# STM32F103.net
KiCad netlist of a schematic drawn in Altium Designer
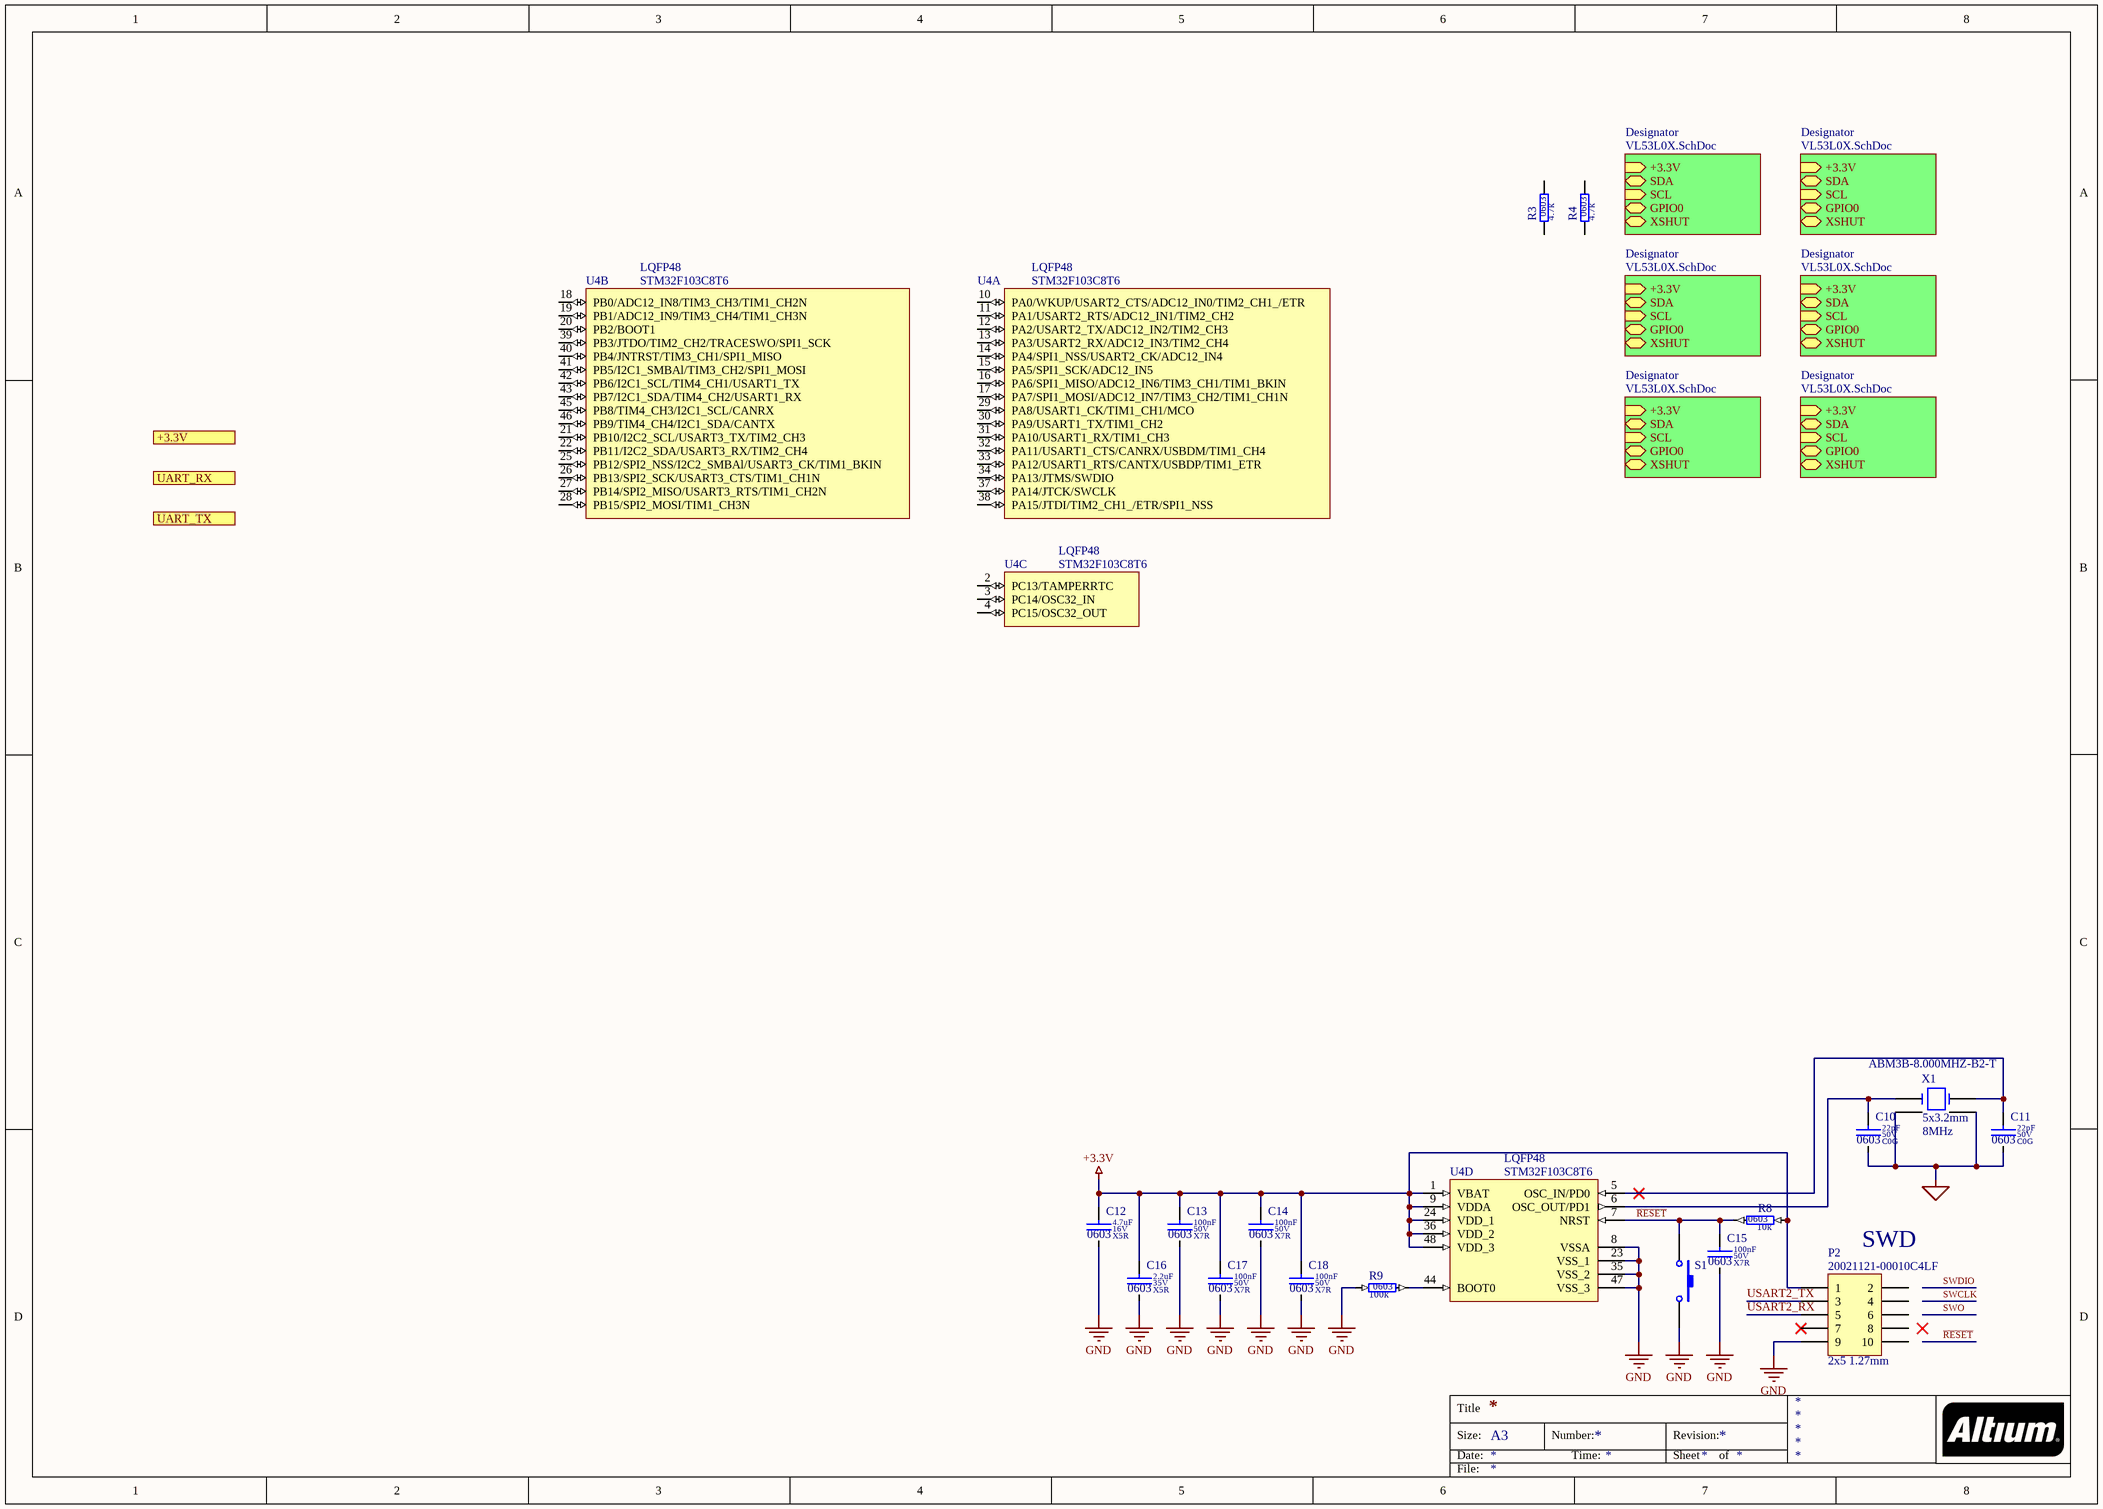
[diagram p0: STM32F103.SchDoc]

(export (version "E")
  (design (tool "Eeschema 10.0.6"))
  (components
    (comp (ref "C10")
      (value "22pF")
      (footprint "C_0603_1608")
      (description "Capacitor")
      (fields
        (field (name "DIELECTRIC") "C0G")
        (field (name "VOLTAGE") "50V")
        (field (name "SCH_FOOTPRINT") "0603")
        (field (name "PART NUMBER") "C_22pF_50V_C0G_0603_5")
        (field (name "MANUFACTURER") "Yageo")
      )
      (libsource (lib "Library") (part "C"))
    )
    (comp (ref "C11")
      (value "22pF")
      (footprint "C_0603_1608")
      (description "Capacitor")
      (fields
        (field (name "DIELECTRIC") "C0G")
        (field (name "VOLTAGE") "50V")
        (field (name "SCH_FOOTPRINT") "0603")
        (field (name "PART NUMBER") "C_22pF_50V_C0G_0603_5")
        (field (name "MANUFACTURER") "Yageo")
      )
      (libsource (lib "Library") (part "C"))
    )
    (comp (ref "C12")
      (value "4.7uF")
      (footprint "C_0603_1608")
      (description "Capacitor")
      (fields
        (field (name "DIELECTRIC") "X5R")
        (field (name "VOLTAGE") "16V")
        (field (name "SCH_FOOTPRINT") "0603")
        (field (name "PART NUMBER") "C_4.7uF_16V_X5R_0603_10")
        (field (name "MANUFACTURER") "Murata")
      )
      (libsource (lib "Library") (part "C"))
    )
    (comp (ref "C13")
      (value "100nF")
      (footprint "C_0603_1608")
      (description "Capacitor")
      (fields
        (field (name "DIELECTRIC") "X7R")
        (field (name "VOLTAGE") "50V")
        (field (name "SCH_FOOTPRINT") "0603")
        (field (name "PART NUMBER") "C_100nF_50V_X7R_0603_5")
        (field (name "MANUFACTURER") "Samsung")
      )
      (libsource (lib "Library") (part "C"))
    )
    (comp (ref "C14")
      (value "100nF")
      (footprint "C_0603_1608")
      (description "Capacitor")
      (fields
        (field (name "DIELECTRIC") "X7R")
        (field (name "VOLTAGE") "50V")
        (field (name "SCH_FOOTPRINT") "0603")
        (field (name "PART NUMBER") "C_100nF_50V_X7R_0603_5")
        (field (name "MANUFACTURER") "Samsung")
      )
      (libsource (lib "Library") (part "C"))
    )
    (comp (ref "C15")
      (value "100nF")
      (footprint "C_0603_1608")
      (description "Capacitor")
      (fields
        (field (name "DIELECTRIC") "X7R")
        (field (name "VOLTAGE") "50V")
        (field (name "SCH_FOOTPRINT") "0603")
        (field (name "PART NUMBER") "C_100nF_50V_X7R_0603_5")
        (field (name "MANUFACTURER") "Samsung")
      )
      (libsource (lib "Library") (part "C"))
    )
    (comp (ref "C16")
      (value "2.2uF")
      (footprint "C_0603_1608")
      (description "Capacitor")
      (fields
        (field (name "DIELECTRIC") "X5R")
        (field (name "VOLTAGE") "35V")
        (field (name "SCH_FOOTPRINT") "0603")
        (field (name "PART NUMBER") "C_2.2uF_35V_X5R_0603_10")
        (field (name "MANUFACTURER") "Murata")
      )
      (libsource (lib "Library") (part "C"))
    )
    (comp (ref "C17")
      (value "100nF")
      (footprint "C_0603_1608")
      (description "Capacitor")
      (fields
        (field (name "DIELECTRIC") "X7R")
        (field (name "VOLTAGE") "50V")
        (field (name "SCH_FOOTPRINT") "0603")
        (field (name "PART NUMBER") "C_100nF_50V_X7R_0603_5")
        (field (name "MANUFACTURER") "Samsung")
      )
      (libsource (lib "Library") (part "C"))
    )
    (comp (ref "C18")
      (value "100nF")
      (footprint "C_0603_1608")
      (description "Capacitor")
      (fields
        (field (name "DIELECTRIC") "X7R")
        (field (name "VOLTAGE") "50V")
        (field (name "SCH_FOOTPRINT") "0603")
        (field (name "PART NUMBER") "C_100nF_50V_X7R_0603_5")
        (field (name "MANUFACTURER") "Samsung")
      )
      (libsource (lib "Library") (part "C"))
    )
    (comp (ref "P2")
      (value "20021121-00010C4LF")
      (footprint "P_HEADER_2x5_1.27")
      (description "Pin Header")
      (fields
        (field (name "PART NUMBER") "P_HEADER_2x5_1.27")
        (field (name "SCH_FOOTPRINT") "2x5 1.27mm")
        (field (name "MANUFACTURER") "FCI")
      )
      (libsource (lib "Library") (part "P_HEADER_2x5"))
    )
    (comp (ref "R3")
      (value "4.7k")
      (footprint "R_0603_1608")
      (fields
        (field (name "SCH_FOOTPRINT") "0603")
        (field (name "PART NUMBER") "R_4.7k_0603_1")
        (field (name "VOLTAGE") "75V")
        (field (name "POWER") "100mW")
      )
      (libsource (lib "Library") (part "R"))
    )
    (comp (ref "R4")
      (value "4.7k")
      (footprint "R_0603_1608")
      (fields
        (field (name "SCH_FOOTPRINT") "0603")
        (field (name "PART NUMBER") "R_4.7k_0603_1")
        (field (name "VOLTAGE") "75V")
        (field (name "POWER") "100mW")
      )
      (libsource (lib "Library") (part "R"))
    )
    (comp (ref "R8")
      (value "10k")
      (footprint "R_0603_1608")
      (fields
        (field (name "SCH_FOOTPRINT") "0603")
        (field (name "PART NUMBER") "R_10k_0603_1")
        (field (name "VOLTAGE") "75V")
        (field (name "POWER") "100mW")
      )
      (libsource (lib "") (part "R_1"))
    )
    (comp (ref "R9")
      (value "100k")
      (footprint "R_0603_1608")
      (fields
        (field (name "SCH_FOOTPRINT") "0603")
        (field (name "PART NUMBER") "R_100k_0603_1")
        (field (name "VOLTAGE") "50V")
        (field (name "POWER") "100mW")
      )
      (libsource (lib "") (part "R_1"))
    )
    (comp (ref "S1")
      (value "3x6mm")
      (footprint "S_TACTSWITCH3x6")
      (description "Tact Switch")
      (fields (field (name "PART NUMBER") "S_TACTSWITCH") (field (name "MANUFACTURER") "Ninigi"))
      (libsource (lib "Library") (part "S_TACTSWITCH"))
    )
    (comp (ref "U4")
      (value "STM32F103C8T6")
      (footprint "LQFP48_7x7")
      (fields
        (field (name "SCH_FOOTPRINT") "LQFP48")
        (field (name "PART NUMBER") "UP_STM32F103C8T6")
        (field (name "MANUFACTURER") "STMicroelectronics")
      )
      (libsource (lib "Library") (part "UP_STM32F103Cx"))
    )
    (comp (ref "X1")
      (value "8MHz")
      (footprint "X_ABM3B_5X3X11")
      (fields
        (field (name "PART NUMBER") "X_ABM3B-8.000MHZ-B2-T")
        (field (name "MANUFACTURER PART NUMBER") "ABM3B-8.000MHZ-B2-T")
        (field (name "SCH_FOOTPRINT") "5x3.2mm")
        (field (name "MANUFACTURER") "Abracon")
      )
      (libsource (lib "Library") (part "X_ABM3B"))
    )
  )
  (nets
    (net (code "1") (name "+3.3V") (class "Default")
      (node (ref "C12") (pin "1") (pinfunction "1_1") (pintype "passive"))
      (node (ref "C13") (pin "1") (pinfunction "1_1") (pintype "passive"))
      (node (ref "C14") (pin "1") (pinfunction "1_1") (pintype "passive"))
      (node (ref "C16") (pin "1") (pinfunction "1_1") (pintype "passive"))
      (node (ref "C17") (pin "1") (pinfunction "1_1") (pintype "passive"))
      (node (ref "C18") (pin "1") (pinfunction "1_1") (pintype "passive"))
      (node (ref "P2") (pin "1") (pinfunction "1_1") (pintype "passive"))
      (node (ref "R8") (pin "1") (pinfunction "1_1") (pintype "input"))
      (node (ref "U4") (pin "1") (pinfunction "VBAT_1") (pintype "input"))
      (node (ref "U4") (pin "24") (pinfunction "VDD_1_24") (pintype "input"))
      (node (ref "U4") (pin "36") (pinfunction "VDD_2_36") (pintype "input"))
      (node (ref "U4") (pin "48") (pinfunction "VDD_3_48") (pintype "input"))
      (node (ref "U4") (pin "9") (pinfunction "VDDA_9") (pintype "input"))
    )
    (net (code "31") (name "/USART2_RX") (class "Default")
      (node (ref "P2") (pin "5") (pinfunction "5_5") (pintype "passive"))
    )
    (net (code "32") (name "/USART2_TX") (class "Default")
      (node (ref "P2") (pin "3") (pinfunction "3_3") (pintype "passive"))
    )
    (net (code "39") (name "/~{RESET}") (class "Default")
      (node (ref "C15") (pin "1") (pinfunction "1_1") (pintype "passive"))
      (node (ref "R8") (pin "2") (pinfunction "2_2") (pintype "output"))
      (node (ref "S1") (pin "1") (pinfunction "1_1") (pintype "passive"))
      (node (ref "U4") (pin "7") (pinfunction "NRST_7") (pintype "input"))
    )
    (net (code "40") (name "GND") (class "Default")
      (node (ref "C10") (pin "2") (pinfunction "2_2") (pintype "passive"))
      (node (ref "C11") (pin "2") (pinfunction "2_2") (pintype "passive"))
      (node (ref "C12") (pin "2") (pinfunction "2_2") (pintype "passive"))
      (node (ref "C13") (pin "2") (pinfunction "2_2") (pintype "passive"))
      (node (ref "C14") (pin "2") (pinfunction "2_2") (pintype "passive"))
      (node (ref "C15") (pin "2") (pinfunction "2_2") (pintype "passive"))
      (node (ref "C16") (pin "2") (pinfunction "2_2") (pintype "passive"))
      (node (ref "C17") (pin "2") (pinfunction "2_2") (pintype "passive"))
      (node (ref "C18") (pin "2") (pinfunction "2_2") (pintype "passive"))
      (node (ref "P2") (pin "9") (pinfunction "9_9") (pintype "passive"))
      (node (ref "R9") (pin "1") (pinfunction "1_1") (pintype "input"))
      (node (ref "S1") (pin "2") (pinfunction "2_2") (pintype "passive"))
      (node (ref "U4") (pin "23") (pinfunction "VSS_1_23") (pintype "power_in"))
      (node (ref "U4") (pin "35") (pinfunction "VSS_2_35") (pintype "power_in"))
      (node (ref "U4") (pin "47") (pinfunction "VSS_3_47") (pintype "power_in"))
      (node (ref "U4") (pin "8") (pinfunction "VSSA_8") (pintype "power_in"))
      (node (ref "X1") (pin "2") (pinfunction "GND_2") (pintype "power_in"))
      (node (ref "X1") (pin "4") (pinfunction "GND_4") (pintype "power_in"))
    )
    (net (code "41") (name "Net-(U4D-BOOT0)") (class "Default")
      (node (ref "R9") (pin "2") (pinfunction "2_2") (pintype "output"))
      (node (ref "U4") (pin "44") (pinfunction "BOOT0_44") (pintype "input"))
    )
    (net (code "42") (name "Net-(U4D-OSC_IN{slash}PD0)") (class "Default")
      (node (ref "C11") (pin "1") (pinfunction "1_1") (pintype "passive"))
      (node (ref "U4") (pin "5") (pinfunction "OSC_IN/PD0_5") (pintype "input"))
      (node (ref "X1") (pin "1") (pinfunction "1_1") (pintype "passive"))
    )
    (net (code "43") (name "Net-(U4D-OSC_OUT{slash}PD1)") (class "Default")
      (node (ref "C10") (pin "1") (pinfunction "1_1") (pintype "passive"))
      (node (ref "U4") (pin "6") (pinfunction "OSC_OUT/PD1_6") (pintype "output"))
      (node (ref "X1") (pin "3") (pinfunction "3_3") (pintype "passive"))
    )
    (net (code "44") (name "unconnected-(P2-Pad2)") (class "Default")
      (node (ref "P2") (pin "2") (pinfunction "2_2") (pintype "passive"))
    )
    (net (code "45") (name "unconnected-(P2-Pad4)") (class "Default")
      (node (ref "P2") (pin "4") (pinfunction "4_4") (pintype "passive"))
    )
    (net (code "46") (name "unconnected-(P2-Pad6)") (class "Default")
      (node (ref "P2") (pin "6") (pinfunction "6_6") (pintype "passive"))
    )
    (net (code "47") (name "unconnected-(P2-Pad7)") (class "Default")
      (node (ref "P2") (pin "7") (pinfunction "7_7") (pintype "passive+no_connect"))
    )
    (net (code "48") (name "unconnected-(P2-Pad8)") (class "Default")
      (node (ref "P2") (pin "8") (pinfunction "8_8") (pintype "passive"))
    )
    (net (code "49") (name "unconnected-(P2-Pad10)") (class "Default")
      (node (ref "P2") (pin "10") (pinfunction "10_10") (pintype "passive"))
    )
    (net (code "50") (name "unconnected-(R3-Pad1)") (class "Default")
      (node (ref "R3") (pin "1") (pinfunction "1_1") (pintype "passive"))
    )
    (net (code "51") (name "unconnected-(R3-Pad2)") (class "Default")
      (node (ref "R3") (pin "2") (pinfunction "2_2") (pintype "passive"))
    )
    (net (code "52") (name "unconnected-(R4-Pad1)") (class "Default")
      (node (ref "R4") (pin "1") (pinfunction "1_1") (pintype "passive"))
    )
    (net (code "53") (name "unconnected-(R4-Pad2)") (class "Default")
      (node (ref "R4") (pin "2") (pinfunction "2_2") (pintype "passive"))
    )
    (net (code "54") (name "unconnected-(U4A-PA0{slash}WKUP{slash}USART2_CTS{slash}ADC12_IN0{slash}TIM2_CH1_{slash}ETR-Pad10)") (class "Default")
      (node (ref "U4") (pin "10") (pinfunction "PA0/WKUP/USART2_CTS/ADC12_IN0/TIM2_CH1_/ETR_10") (pintype "bidirectional"))
    )
    (net (code "55") (name "unconnected-(U4A-PA1{slash}USART2_RTS{slash}ADC12_IN1{slash}TIM2_CH2-Pad11)") (class "Default")
      (node (ref "U4") (pin "11") (pinfunction "PA1/USART2_RTS/ADC12_IN1/TIM2_CH2_11") (pintype "bidirectional"))
    )
    (net (code "56") (name "unconnected-(U4A-PA2{slash}USART2_TX{slash}ADC12_IN2{slash}TIM2_CH3-Pad12)") (class "Default")
      (node (ref "U4") (pin "12") (pinfunction "PA2/USART2_TX/ADC12_IN2/TIM2_CH3_12") (pintype "bidirectional"))
    )
    (net (code "57") (name "unconnected-(U4A-PA3{slash}USART2_RX{slash}ADC12_IN3{slash}TIM2_CH4-Pad13)") (class "Default")
      (node (ref "U4") (pin "13") (pinfunction "PA3/USART2_RX/ADC12_IN3/TIM2_CH4_13") (pintype "bidirectional"))
    )
    (net (code "58") (name "unconnected-(U4A-PA4{slash}SPI1_NSS{slash}USART2_CK{slash}ADC12_IN4-Pad14)") (class "Default")
      (node (ref "U4") (pin "14") (pinfunction "PA4/SPI1_NSS/USART2_CK/ADC12_IN4_14") (pintype "bidirectional"))
    )
    (net (code "59") (name "unconnected-(U4A-PA5{slash}SPI1_SCK{slash}ADC12_IN5-Pad15)") (class "Default")
      (node (ref "U4") (pin "15") (pinfunction "PA5/SPI1_SCK/ADC12_IN5_15") (pintype "bidirectional"))
    )
    (net (code "60") (name "unconnected-(U4A-PA6{slash}SPI1_MISO{slash}ADC12_IN6{slash}TIM3_CH1{slash}TIM1_BKIN-Pad16)") (class "Default")
      (node (ref "U4") (pin "16") (pinfunction "PA6/SPI1_MISO/ADC12_IN6/TIM3_CH1/TIM1_BKIN_16") (pintype "bidirectional"))
    )
    (net (code "61") (name "unconnected-(U4A-PA7{slash}SPI1_MOSI{slash}ADC12_IN7{slash}TIM3_CH2{slash}TIM1_CH1N-Pad17)") (class "Default")
      (node (ref "U4") (pin "17") (pinfunction "PA7/SPI1_MOSI/ADC12_IN7/TIM3_CH2/TIM1_CH1N_17") (pintype "bidirectional"))
    )
    (net (code "62") (name "unconnected-(U4A-PA8{slash}USART1_CK{slash}TIM1_CH1{slash}MCO-Pad29)") (class "Default")
      (node (ref "U4") (pin "29") (pinfunction "PA8/USART1_CK/TIM1_CH1/MCO_29") (pintype "bidirectional"))
    )
    (net (code "63") (name "unconnected-(U4A-PA9{slash}USART1_TX{slash}TIM1_CH2-Pad30)") (class "Default")
      (node (ref "U4") (pin "30") (pinfunction "PA9/USART1_TX/TIM1_CH2_30") (pintype "bidirectional"))
    )
    (net (code "64") (name "unconnected-(U4A-PA10{slash}USART1_RX{slash}TIM1_CH3-Pad31)") (class "Default")
      (node (ref "U4") (pin "31") (pinfunction "PA10/USART1_RX/TIM1_CH3_31") (pintype "bidirectional"))
    )
    (net (code "65") (name "unconnected-(U4A-PA11{slash}USART1_CTS{slash}CANRX{slash}USBDM{slash}TIM1_CH4-Pad32)") (class "Default")
      (node (ref "U4") (pin "32") (pinfunction "PA11/USART1_CTS/CANRX/USBDM/TIM1_CH4_32") (pintype "bidirectional"))
    )
    (net (code "66") (name "unconnected-(U4A-PA12{slash}USART1_RTS{slash}CANTX{slash}USBDP{slash}TIM1_ETR-Pad33)") (class "Default")
      (node (ref "U4") (pin "33") (pinfunction "PA12/USART1_RTS/CANTX/USBDP/TIM1_ETR_33") (pintype "bidirectional"))
    )
    (net (code "67") (name "unconnected-(U4A-PA13{slash}JTMS{slash}SWDIO-Pad34)") (class "Default")
      (node (ref "U4") (pin "34") (pinfunction "PA13/JTMS/SWDIO_34") (pintype "bidirectional"))
    )
    (net (code "68") (name "unconnected-(U4A-PA14{slash}JTCK{slash}SWCLK-Pad37)") (class "Default")
      (node (ref "U4") (pin "37") (pinfunction "PA14/JTCK/SWCLK_37") (pintype "bidirectional"))
    )
    (net (code "69") (name "unconnected-(U4A-PA15{slash}JTDI{slash}TIM2_CH1_{slash}ETR{slash}SPI1_NSS-Pad38)") (class "Default")
      (node (ref "U4") (pin "38") (pinfunction "PA15/JTDI/TIM2_CH1_/ETR/SPI1_NSS_38") (pintype "bidirectional"))
    )
    (net (code "70") (name "unconnected-(U4B-PB0{slash}ADC12_IN8{slash}TIM3_CH3{slash}TIM1_CH2N-Pad18)") (class "Default")
      (node (ref "U4") (pin "18") (pinfunction "PB0/ADC12_IN8/TIM3_CH3/TIM1_CH2N_18") (pintype "bidirectional"))
    )
    (net (code "71") (name "unconnected-(U4B-PB1{slash}ADC12_IN9{slash}TIM3_CH4{slash}TIM1_CH3N-Pad19)") (class "Default")
      (node (ref "U4") (pin "19") (pinfunction "PB1/ADC12_IN9/TIM3_CH4/TIM1_CH3N_19") (pintype "bidirectional"))
    )
    (net (code "72") (name "unconnected-(U4B-PB2{slash}BOOT1-Pad20)") (class "Default")
      (node (ref "U4") (pin "20") (pinfunction "PB2/BOOT1_20") (pintype "bidirectional"))
    )
    (net (code "73") (name "unconnected-(U4B-PB3{slash}JTDO{slash}TIM2_CH2{slash}TRACESWO{slash}SPI1_SCK-Pad39)") (class "Default")
      (node (ref "U4") (pin "39") (pinfunction "PB3/JTDO/TIM2_CH2/TRACESWO/SPI1_SCK_39") (pintype "bidirectional"))
    )
    (net (code "74") (name "unconnected-(U4B-PB4{slash}JNTRST{slash}TIM3_CH1{slash}SPI1_MISO-Pad40)") (class "Default")
      (node (ref "U4") (pin "40") (pinfunction "PB4/JNTRST/TIM3_CH1/SPI1_MISO_40") (pintype "bidirectional"))
    )
    (net (code "75") (name "unconnected-(U4B-PB5{slash}I2C1_SMBAl{slash}TIM3_CH2{slash}SPI1_MOSI-Pad41)") (class "Default")
      (node (ref "U4") (pin "41") (pinfunction "PB5/I2C1_SMBAl/TIM3_CH2/SPI1_MOSI_41") (pintype "bidirectional"))
    )
    (net (code "76") (name "unconnected-(U4B-PB6{slash}I2C1_SCL{slash}TIM4_CH1{slash}USART1_TX-Pad42)") (class "Default")
      (node (ref "U4") (pin "42") (pinfunction "PB6/I2C1_SCL/TIM4_CH1/USART1_TX_42") (pintype "bidirectional"))
    )
    (net (code "77") (name "unconnected-(U4B-PB7{slash}I2C1_SDA{slash}TIM4_CH2{slash}USART1_RX-Pad43)") (class "Default")
      (node (ref "U4") (pin "43") (pinfunction "PB7/I2C1_SDA/TIM4_CH2/USART1_RX_43") (pintype "bidirectional"))
    )
    (net (code "78") (name "unconnected-(U4B-PB8{slash}TIM4_CH3{slash}I2C1_SCL{slash}CANRX-Pad45)") (class "Default")
      (node (ref "U4") (pin "45") (pinfunction "PB8/TIM4_CH3/I2C1_SCL/CANRX_45") (pintype "bidirectional"))
    )
    (net (code "79") (name "unconnected-(U4B-PB9{slash}TIM4_CH4{slash}I2C1_SDA{slash}CANTX-Pad46)") (class "Default")
      (node (ref "U4") (pin "46") (pinfunction "PB9/TIM4_CH4/I2C1_SDA/CANTX_46") (pintype "bidirectional"))
    )
    (net (code "80") (name "unconnected-(U4B-PB10{slash}I2C2_SCL{slash}USART3_TX{slash}TIM2_CH3-Pad21)") (class "Default")
      (node (ref "U4") (pin "21") (pinfunction "PB10/I2C2_SCL/USART3_TX/TIM2_CH3_21") (pintype "bidirectional"))
    )
    (net (code "81") (name "unconnected-(U4B-PB11{slash}I2C2_SDA{slash}USART3_RX{slash}TIM2_CH4-Pad22)") (class "Default")
      (node (ref "U4") (pin "22") (pinfunction "PB11/I2C2_SDA/USART3_RX/TIM2_CH4_22") (pintype "bidirectional"))
    )
    (net (code "82") (name "unconnected-(U4B-PB12{slash}SPI2_NSS{slash}I2C2_SMBAl{slash}USART3_CK{slash}TIM1_BKIN-Pad25)") (class "Default")
      (node (ref "U4") (pin "25") (pinfunction "PB12/SPI2_NSS/I2C2_SMBAl/USART3_CK/TIM1_BKIN_25") (pintype "bidirectional"))
    )
    (net (code "83") (name "unconnected-(U4B-PB13{slash}SPI2_SCK{slash}USART3_CTS{slash}TIM1_CH1N-Pad26)") (class "Default")
      (node (ref "U4") (pin "26") (pinfunction "PB13/SPI2_SCK/USART3_CTS/TIM1_CH1N_26") (pintype "bidirectional"))
    )
    (net (code "84") (name "unconnected-(U4B-PB14{slash}SPI2_MISO{slash}USART3_RTS{slash}TIM1_CH2N-Pad27)") (class "Default")
      (node (ref "U4") (pin "27") (pinfunction "PB14/SPI2_MISO/USART3_RTS/TIM1_CH2N_27") (pintype "bidirectional"))
    )
    (net (code "85") (name "unconnected-(U4B-PB15{slash}SPI2_MOSI{slash}TIM1_CH3N-Pad28)") (class "Default")
      (node (ref "U4") (pin "28") (pinfunction "PB15/SPI2_MOSI/TIM1_CH3N_28") (pintype "bidirectional"))
    )
    (net (code "86") (name "unconnected-(U4C-PC13{slash}TAMPERRTC-Pad2)") (class "Default")
      (node (ref "U4") (pin "2") (pinfunction "PC13/TAMPERRTC_2") (pintype "bidirectional"))
    )
    (net (code "87") (name "unconnected-(U4C-PC14{slash}OSC32_IN-Pad3)") (class "Default")
      (node (ref "U4") (pin "3") (pinfunction "PC14/OSC32_IN_3") (pintype "bidirectional"))
    )
    (net (code "88") (name "unconnected-(U4C-PC15{slash}OSC32_OUT-Pad4)") (class "Default")
      (node (ref "U4") (pin "4") (pinfunction "PC15/OSC32_OUT_4") (pintype "bidirectional"))
    )
  )
)
